# picopower.net
KiCad netlist of a schematic drawn in EAGLE
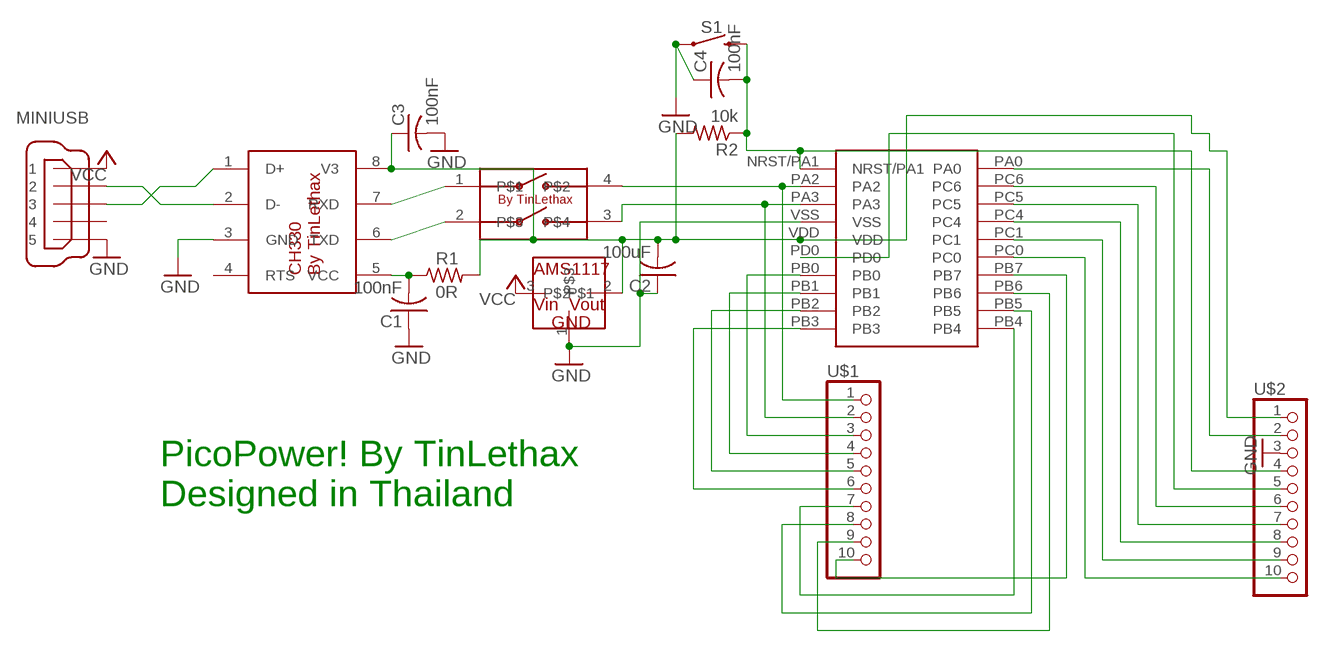
[diagram p0: schematic, sheet 1]

(export (version "E")
  (design (tool "Eeschema 10.0.6"))
  (components
    (comp (ref "2DIP")
      (value "2DIPSWITCH")
      (footprint "eagle-import:SOIC127P835X230-4N")
      (libsource (lib "eagle-import") (part "2DIPSWITCH"))
    )
    (comp (ref "C1")
      (value "100nF")
      (footprint "eagle-import:C0603K")
      (libsource (lib "eagle-import") (part "C-USC0603K"))
    )
    (comp (ref "C2")
      (value "100uF")
      (footprint "eagle-import:C0603K")
      (libsource (lib "eagle-import") (part "C-USC0603K"))
    )
    (comp (ref "C3")
      (value "100nF")
      (footprint "eagle-import:C0603K")
      (libsource (lib "eagle-import") (part "C-USC0603K"))
    )
    (comp (ref "C4")
      (value "100nF")
      (footprint "eagle-import:C0603K")
      (libsource (lib "eagle-import") (part "C-USC0603K"))
    )
    (comp (ref "CH330")
      (value "CH330")
      (footprint "eagle-import:SOIC127P600X150-8N")
      (libsource (lib "eagle-import") (part "CH330"))
    )
    (comp (ref "MINIUSB")
      (value "MINI-USB-UX60A-MB-5ST")
      (footprint "eagle-import:UX60A-MB-5ST")
      (libsource (lib "eagle-import") (part "MINI-USB-UX60A-MB-5ST"))
    )
    (comp (ref "R1")
      (value "0R")
      (footprint "eagle-import:R0603")
      (libsource (lib "eagle-import") (part "R-US_R0603"))
    )
    (comp (ref "R2")
      (value "10k")
      (footprint "eagle-import:R0603")
      (libsource (lib "eagle-import") (part "R-US_R0603"))
    )
    (comp (ref "S1")
      (value "MOMENTARY-SWITCH-SPST-SMD-6.0X3.5MM")
      (footprint "eagle-import:TACTILE_SWITCH_SMD_6.0X3.5MM")
      (libsource (lib "eagle-import") (part "MOMENTARY-SWITCH-SPST-SMD-6.0X3.5MM"))
    )
    (comp (ref "STM8L")
      (value "STM8L151F3")
      (footprint "eagle-import:UFQFPN-20")
      (libsource (lib "eagle-import") (part "STM8L151F3"))
    )
    (comp (ref "U$1")
      (value "PINHD-1X10")
      (footprint "eagle-import:1X10-BIG")
      (libsource (lib "eagle-import") (part "PINHD-1X10"))
    )
    (comp (ref "U$2")
      (value "PINHD-1X10")
      (footprint "eagle-import:1X10-BIG")
      (libsource (lib "eagle-import") (part "PINHD-1X10"))
    )
    (comp (ref "U$3")
      (value "AMS1117")
      (footprint "eagle-import:SOT223")
      (libsource (lib "eagle-import") (part "AMS1117"))
    )
  )
  (nets
    (net (code "1") (name "GND") (class "Default")
      (node (ref "C1") (pin "1") (pinfunction "1_1") (pintype "passive"))
      (node (ref "C2") (pin "1") (pinfunction "1_1") (pintype "passive"))
      (node (ref "C3") (pin "2") (pinfunction "2_2") (pintype "passive"))
      (node (ref "C4") (pin "1") (pinfunction "1_1") (pintype "passive"))
      (node (ref "CH330") (pin "3") (pinfunction "GND_3") (pintype "bidirectional"))
      (node (ref "MINIUSB") (pin "5") (pinfunction "5_5") (pintype "input"))
      (node (ref "S1") (pin "1") (pinfunction "1_1") (pintype "passive"))
      (node (ref "STM8L") (pin "VSS") (pinfunction "VSS_VSS") (pintype "bidirectional"))
      (node (ref "U$2") (pin "3") (pinfunction "3_3") (pintype "passive"))
      (node (ref "U$3") (pin "1") (pinfunction "P$3_1") (pintype "bidirectional"))
    )
    (net (code "2") (name "Net-(2DIP-P$1)") (class "Default")
      (node (ref "2DIP") (pin "1") (pinfunction "P$1_1") (pintype "bidirectional"))
      (node (ref "CH330") (pin "7") (pinfunction "RXD_7") (pintype "bidirectional"))
    )
    (net (code "3") (name "Net-(2DIP-P$2)") (class "Default")
      (node (ref "2DIP") (pin "4") (pinfunction "P$2_4") (pintype "bidirectional"))
      (node (ref "STM8L") (pin "PA2") (pinfunction "PA2_PA2") (pintype "bidirectional"))
      (node (ref "U$1") (pin "1") (pinfunction "1_1") (pintype "passive"))
    )
    (net (code "4") (name "Net-(2DIP-P$3)") (class "Default")
      (node (ref "2DIP") (pin "2") (pinfunction "P$3_2") (pintype "bidirectional"))
      (node (ref "CH330") (pin "6") (pinfunction "TXD_6") (pintype "bidirectional"))
    )
    (net (code "5") (name "Net-(2DIP-P$4)") (class "Default")
      (node (ref "2DIP") (pin "3") (pinfunction "P$4_3") (pintype "bidirectional"))
      (node (ref "STM8L") (pin "PA3") (pinfunction "PA3_PA3") (pintype "bidirectional"))
      (node (ref "U$1") (pin "2") (pinfunction "2_2") (pintype "passive"))
    )
    (net (code "6") (name "Net-(C4-Pad2)") (class "Default")
      (node (ref "C4") (pin "2") (pinfunction "2_2") (pintype "passive"))
      (node (ref "R2") (pin "1") (pinfunction "1_1") (pintype "passive"))
      (node (ref "S1") (pin "2") (pinfunction "2_2") (pintype "passive"))
      (node (ref "STM8L") (pin "NRST/PA1") (pinfunction "NRST/PA1_NRST/PA1") (pintype "bidirectional"))
      (node (ref "U$2") (pin "4") (pinfunction "4_4") (pintype "passive"))
    )
    (net (code "7") (name "Net-(CH330-D+)") (class "Default")
      (node (ref "CH330") (pin "1") (pinfunction "D+_1") (pintype "bidirectional"))
      (node (ref "MINIUSB") (pin "3") (pinfunction "3_3") (pintype "input"))
    )
    (net (code "8") (name "Net-(CH330-D-)") (class "Default")
      (node (ref "CH330") (pin "2") (pinfunction "D-_2") (pintype "bidirectional"))
      (node (ref "MINIUSB") (pin "2") (pinfunction "2_2") (pintype "input"))
    )
    (net (code "9") (name "Net-(CH330-V3)") (class "Default")
      (node (ref "C2") (pin "2") (pinfunction "2_2") (pintype "passive"))
      (node (ref "C3") (pin "1") (pinfunction "1_1") (pintype "passive"))
      (node (ref "CH330") (pin "8") (pinfunction "V3_8") (pintype "bidirectional"))
      (node (ref "R1") (pin "2") (pinfunction "2_2") (pintype "passive"))
      (node (ref "R2") (pin "2") (pinfunction "2_2") (pintype "passive"))
      (node (ref "STM8L") (pin "VDD") (pinfunction "VDD_VDD") (pintype "bidirectional"))
      (node (ref "U$2") (pin "1") (pinfunction "1_1") (pintype "passive"))
      (node (ref "U$3") (pin "2") (pinfunction "P$2_2") (pintype "bidirectional"))
    )
    (net (code "10") (name "Net-(CH330-VCC)") (class "Default")
      (node (ref "C1") (pin "2") (pinfunction "2_2") (pintype "passive"))
      (node (ref "CH330") (pin "5") (pinfunction "VCC_5") (pintype "bidirectional"))
      (node (ref "R1") (pin "1") (pinfunction "1_1") (pintype "passive"))
    )
    (net (code "11") (name "Net-(STM8L-PadPA0)") (class "Default")
      (node (ref "STM8L") (pin "PA0") (pinfunction "PA0_PA0") (pintype "bidirectional"))
      (node (ref "U$2") (pin "2") (pinfunction "2_2") (pintype "passive"))
    )
    (net (code "12") (name "Net-(STM8L-PadPB0)") (class "Default")
      (node (ref "STM8L") (pin "PB0") (pinfunction "PB0_PB0") (pintype "bidirectional"))
      (node (ref "U$1") (pin "3") (pinfunction "3_3") (pintype "passive"))
    )
    (net (code "13") (name "Net-(STM8L-PadPB1)") (class "Default")
      (node (ref "STM8L") (pin "PB1") (pinfunction "PB1_PB1") (pintype "bidirectional"))
      (node (ref "U$1") (pin "4") (pinfunction "4_4") (pintype "passive"))
    )
    (net (code "14") (name "Net-(STM8L-PadPB2)") (class "Default")
      (node (ref "STM8L") (pin "PB2") (pinfunction "PB2_PB2") (pintype "bidirectional"))
      (node (ref "U$1") (pin "5") (pinfunction "5_5") (pintype "passive"))
    )
    (net (code "15") (name "Net-(STM8L-PadPB3)") (class "Default")
      (node (ref "STM8L") (pin "PB3") (pinfunction "PB3_PB3") (pintype "bidirectional"))
      (node (ref "U$1") (pin "6") (pinfunction "6_6") (pintype "passive"))
    )
    (net (code "16") (name "Net-(STM8L-PadPB4)") (class "Default")
      (node (ref "STM8L") (pin "PB4") (pinfunction "PB4_PB4") (pintype "bidirectional"))
      (node (ref "U$1") (pin "7") (pinfunction "7_7") (pintype "passive"))
    )
    (net (code "17") (name "Net-(STM8L-PadPB5)") (class "Default")
      (node (ref "STM8L") (pin "PB5") (pinfunction "PB5_PB5") (pintype "bidirectional"))
      (node (ref "U$1") (pin "8") (pinfunction "8_8") (pintype "passive"))
    )
    (net (code "18") (name "Net-(STM8L-PadPB6)") (class "Default")
      (node (ref "STM8L") (pin "PB6") (pinfunction "PB6_PB6") (pintype "bidirectional"))
      (node (ref "U$1") (pin "9") (pinfunction "9_9") (pintype "passive"))
    )
    (net (code "19") (name "Net-(STM8L-PadPB7)") (class "Default")
      (node (ref "STM8L") (pin "PB7") (pinfunction "PB7_PB7") (pintype "bidirectional"))
      (node (ref "U$1") (pin "10") (pinfunction "10_10") (pintype "passive"))
    )
    (net (code "20") (name "Net-(STM8L-PadPC0)") (class "Default")
      (node (ref "STM8L") (pin "PC0") (pinfunction "PC0_PC0") (pintype "bidirectional"))
      (node (ref "U$2") (pin "10") (pinfunction "10_10") (pintype "passive"))
    )
    (net (code "21") (name "Net-(STM8L-PadPC1)") (class "Default")
      (node (ref "STM8L") (pin "PC1") (pinfunction "PC1_PC1") (pintype "bidirectional"))
      (node (ref "U$2") (pin "9") (pinfunction "9_9") (pintype "passive"))
    )
    (net (code "22") (name "Net-(STM8L-PadPC4)") (class "Default")
      (node (ref "STM8L") (pin "PC4") (pinfunction "PC4_PC4") (pintype "bidirectional"))
      (node (ref "U$2") (pin "8") (pinfunction "8_8") (pintype "passive"))
    )
    (net (code "23") (name "Net-(STM8L-PadPC5)") (class "Default")
      (node (ref "STM8L") (pin "PC5") (pinfunction "PC5_PC5") (pintype "bidirectional"))
      (node (ref "U$2") (pin "7") (pinfunction "7_7") (pintype "passive"))
    )
    (net (code "24") (name "Net-(STM8L-PadPC6)") (class "Default")
      (node (ref "STM8L") (pin "PC6") (pinfunction "PC6_PC6") (pintype "bidirectional"))
      (node (ref "U$2") (pin "6") (pinfunction "6_6") (pintype "passive"))
    )
    (net (code "25") (name "Net-(STM8L-PadPD0)") (class "Default")
      (node (ref "STM8L") (pin "PD0") (pinfunction "PD0_PD0") (pintype "bidirectional"))
      (node (ref "U$2") (pin "5") (pinfunction "5_5") (pintype "passive"))
    )
    (net (code "26") (name "VCC") (class "Default")
      (node (ref "MINIUSB") (pin "1") (pinfunction "1_1") (pintype "input"))
      (node (ref "U$3") (pin "3") (pinfunction "P$1_3") (pintype "bidirectional"))
    )
    (net (code "27") (name "unconnected-(CH330-RTS-Pad4)") (class "Default")
      (node (ref "CH330") (pin "4") (pinfunction "RTS_4") (pintype "bidirectional"))
    )
    (net (code "28") (name "unconnected-(MINIUSB-Pad4)") (class "Default")
      (node (ref "MINIUSB") (pin "4") (pinfunction "4_4") (pintype "input"))
    )
  )
)
